# PIC32MZ.net
KiCad netlist of a schematic drawn in Altium Designer
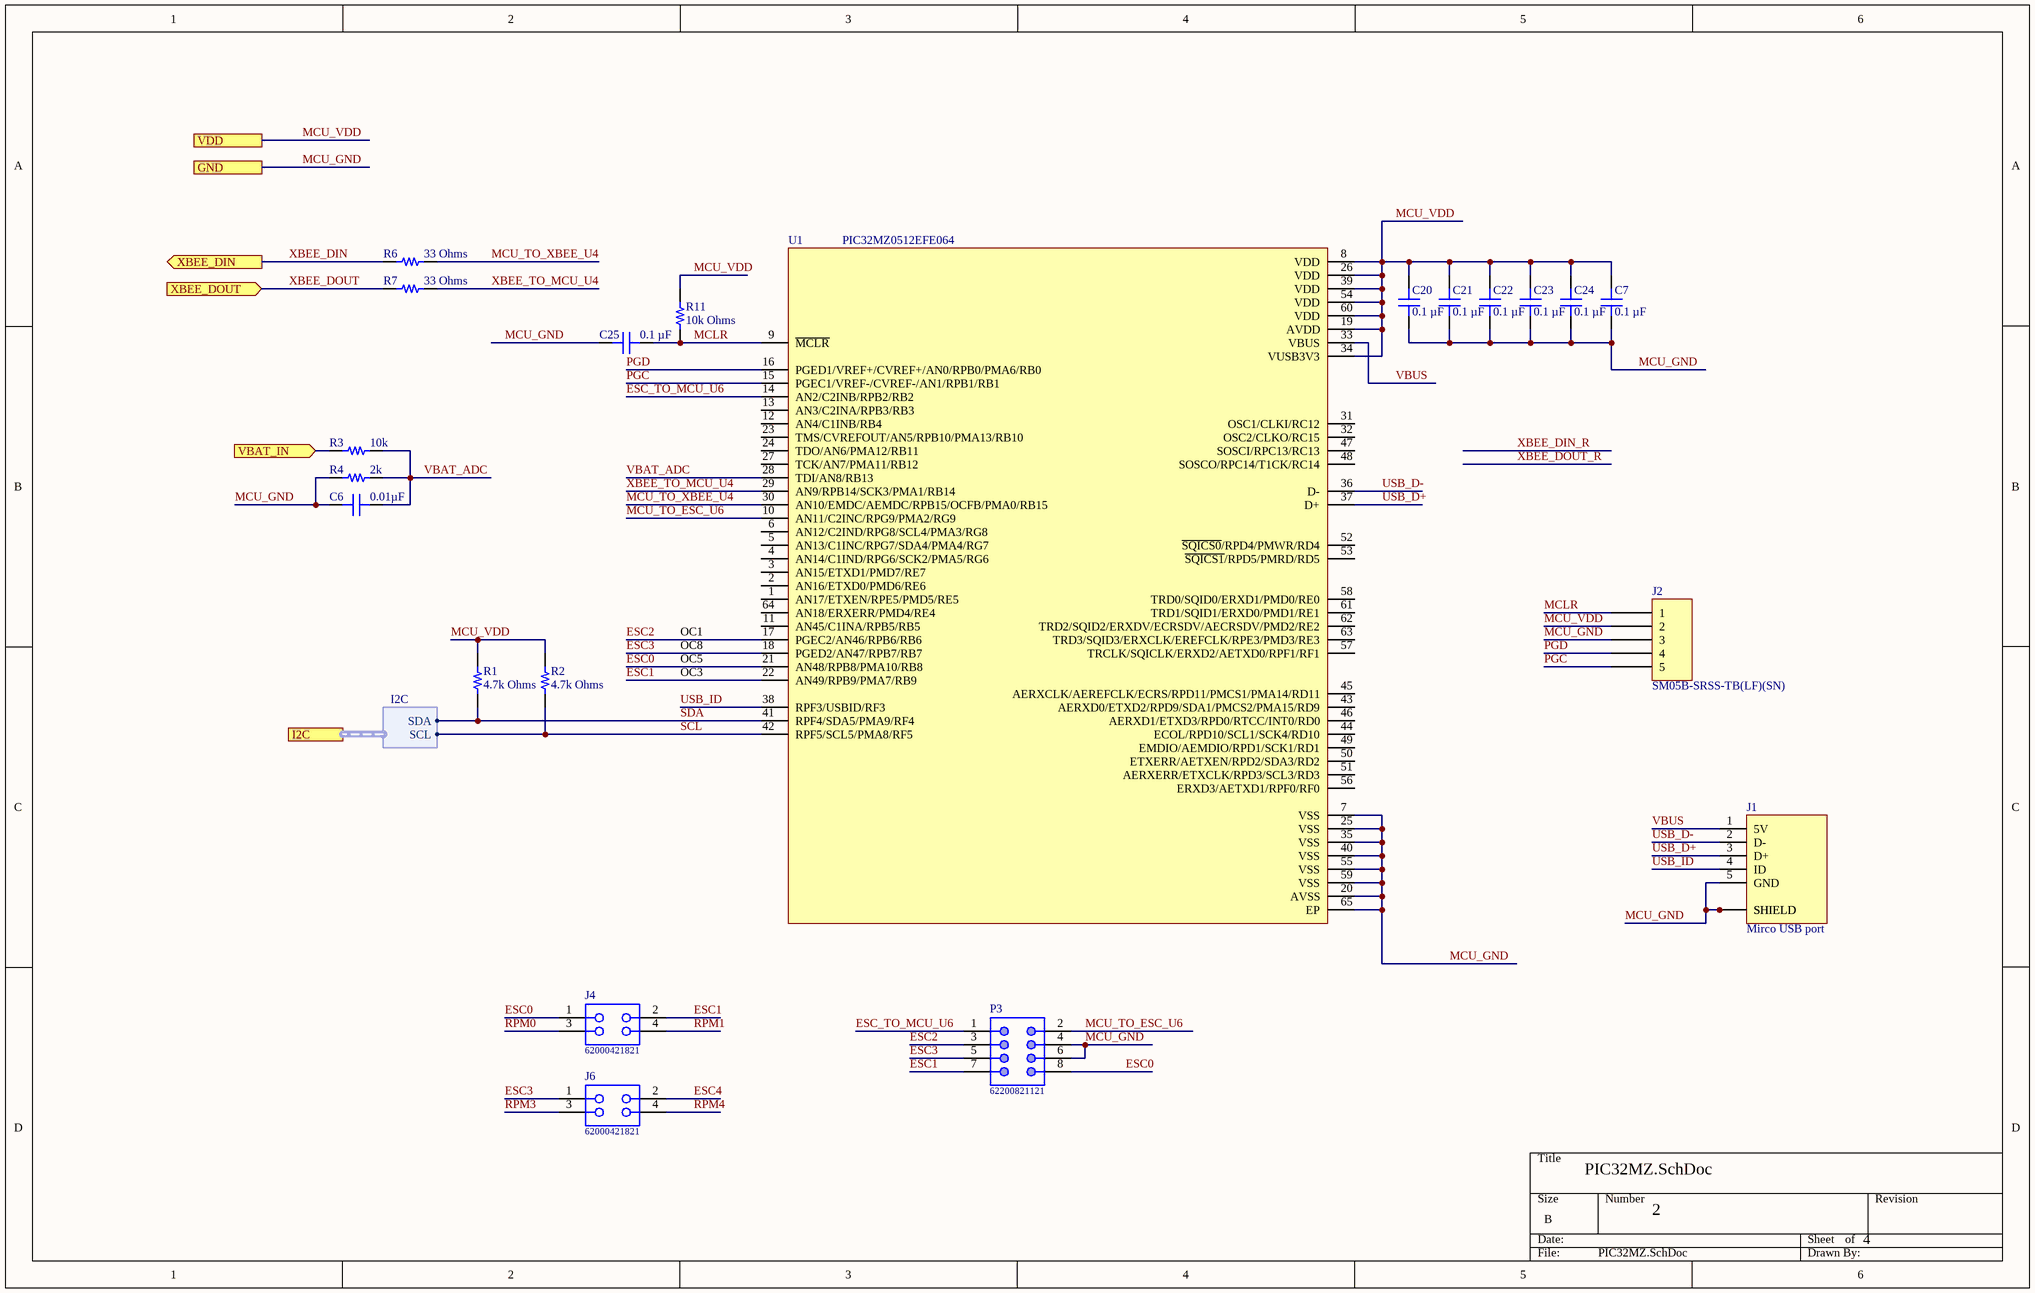
[diagram p0: PIC32MZ.SchDoc]

(export (version "E")
  (design (tool "Eeschema 10.0.6"))
  (components
    (comp (ref "C6")
      (value "0.01µF")
      (footprint "CAP 0603_1608")
      (description "CAP CER 0.1UF 100V 0603 EPOXY")
      (fields
        (field (name "PART NUMBER") "GCG188R92A104KA03D")
        (field (name "MANUFACTURER") "Murata Electronics")
      )
      (libsource (lib "Celestial Altium Library - altium_library") (part "Capacitor"))
    )
    (comp (ref "C7")
      (value "0.1 µF")
      (footprint "CAP 0402_1005")
      (description "CAP CER 0.1UF 16V X7R 0402")
      (fields (field (name "PART NUMBER") "C0402C104K4RACAUTO") (field (name "MANUFACTURER") "KEMET"))
      (libsource (lib "Celestial Altium Library - altium_library") (part "Capacitor"))
    )
    (comp (ref "C20")
      (value "0.1 µF")
      (footprint "CAP 0402_1005")
      (description "CAP CER 0.1UF 16V X7R 0402")
      (fields (field (name "PART NUMBER") "C0402C104K4RACAUTO") (field (name "MANUFACTURER") "KEMET"))
      (libsource (lib "Celestial Altium Library - altium_library") (part "Capacitor"))
    )
    (comp (ref "C21")
      (value "0.1 µF")
      (footprint "CAP 0402_1005")
      (description "CAP CER 0.1UF 16V X7R 0402")
      (fields (field (name "PART NUMBER") "C0402C104K4RACAUTO") (field (name "MANUFACTURER") "KEMET"))
      (libsource (lib "Celestial Altium Library - altium_library") (part "Capacitor"))
    )
    (comp (ref "C22")
      (value "0.1 µF")
      (footprint "CAP 0402_1005")
      (description "CAP CER 0.1UF 16V X7R 0402")
      (fields (field (name "PART NUMBER") "C0402C104K4RACAUTO") (field (name "MANUFACTURER") "KEMET"))
      (libsource (lib "Celestial Altium Library - altium_library") (part "Capacitor"))
    )
    (comp (ref "C23")
      (value "0.1 µF")
      (footprint "CAP 0402_1005")
      (description "CAP CER 0.1UF 16V X7R 0402")
      (fields (field (name "PART NUMBER") "C0402C104K4RACAUTO") (field (name "MANUFACTURER") "KEMET"))
      (libsource (lib "Celestial Altium Library - altium_library") (part "Capacitor"))
    )
    (comp (ref "C24")
      (value "0.1 µF")
      (footprint "CAP 0402_1005")
      (description "CAP CER 0.1UF 16V X7R 0402")
      (fields (field (name "PART NUMBER") "C0402C104K4RACAUTO") (field (name "MANUFACTURER") "KEMET"))
      (libsource (lib "Celestial Altium Library - altium_library") (part "Capacitor"))
    )
    (comp (ref "C25")
      (value "0.1 µF")
      (footprint "CAP 0402_1005")
      (description "CAP CER 0.1UF 16V X7R 0402")
      (fields (field (name "PART NUMBER") "C0402C104K4RACAUTO") (field (name "MANUFACTURER") "KEMET"))
      (libsource (lib "Celestial Altium Library - altium_library") (part "Capacitor"))
    )
    (comp (ref "J1")
      (value "Mirco USB port")
      (footprint "AMPHENOL_10118194-0001LF")
      (description "USB - micro B USB 2.0 Receptacle Connector 5 Position Surface Mount, Right Angle; Through Hole")
      (fields (field (name "MF") "Amphenol ICC") (field (name "MP") "10118194-0001LF"))
      (libsource (lib "IC") (part "10118194-0001LF"))
    )
    (comp (ref "J2")
      (value "SM05B-SRSS-TB(LF)(SN)")
      (footprint "JST SM05B-SRSS-TB")
      (description "CONN HEADER SMD R/A 5POS 1MM")
      (fields (field (name "MANUFACTURER") "JST Sales America Inc."))
      (libsource (lib "Celestial Altium Library - altium_library") (part "5 Pin"))
    )
    (comp (ref "J4")
      (value "62000421821")
      (footprint "62000421821")
      (description "WR-PHD Socket Header, THT, pitch 2mm, Dual Row, Vertical, 4p")
      (fields (field (name "MANUFACTURER") "Wurth Elektronik"))
      (libsource (lib "Altium_WR-PHD") (part "62000421821"))
    )
    (comp (ref "J6")
      (value "62000421821")
      (footprint "62000421821")
      (description "WR-PHD Socket Header, THT, pitch 2mm, Dual Row, Vertical, 4p")
      (fields (field (name "MANUFACTURER") "Wurth Elektronik"))
      (libsource (lib "Altium_WR-PHD") (part "62000421821"))
    )
    (comp (ref "P3")
      (value "62200821121")
      (footprint "62200821121")
      (description "WR-PHD Pin Header, THT, pitch 1.27mm, Dual Row, Vertical, 8p")
      (fields (field (name "MANUFACTURER") "Wurth Elektronik"))
      (libsource (lib "Altium_WR-PHD") (part "62200821121"))
    )
    (comp (ref "R1")
      (value "4.7k Ohms")
      (footprint "RES 0402_1005")
      (description "RES 330 OHM 5% 1/16W 0402")
      (fields (field (name "PART NUMBER") "CRCW0402330RJNEDC") (field (name "MANUFACTURER") "Vishay Dale"))
      (libsource (lib "Celestial Altium Library - altium_library") (part "Resistor"))
    )
    (comp (ref "R2")
      (value "4.7k Ohms")
      (footprint "RES 0402_1005")
      (description "RES 330 OHM 5% 1/16W 0402")
      (fields (field (name "PART NUMBER") "CRCW0402330RJNEDC") (field (name "MANUFACTURER") "Vishay Dale"))
      (libsource (lib "Celestial Altium Library - altium_library") (part "Resistor"))
    )
    (comp (ref "R3")
      (value "10k")
      (footprint "RES 0603_1608")
      (description "RES SMD 21.5 OHM 1% 1/10W 0603")
      (fields
        (field (name "PART NUMBER") "ERJ-3EKF21R5V")
        (field (name "MANUFACTURER") "Panasonic Electronic Components")
      )
      (libsource (lib "Celestial Altium Library - altium_library") (part "Resistor"))
    )
    (comp (ref "R4")
      (value "2k")
      (footprint "RES 0603_1608")
      (description "RES SMD 21.5 OHM 1% 1/10W 0603")
      (fields
        (field (name "PART NUMBER") "ERJ-3EKF21R5V")
        (field (name "MANUFACTURER") "Panasonic Electronic Components")
      )
      (libsource (lib "Celestial Altium Library - altium_library") (part "Resistor"))
    )
    (comp (ref "R6")
      (value "33 Ohms")
      (footprint "RES 0402_1005")
      (description "RES 330 OHM 5% 1/16W 0402")
      (fields (field (name "PART NUMBER") "CRCW0402330RJNEDC") (field (name "MANUFACTURER") "Vishay Dale"))
      (libsource (lib "Celestial Altium Library - altium_library") (part "Resistor"))
    )
    (comp (ref "R7")
      (value "33 Ohms")
      (footprint "RES 0402_1005")
      (description "RES 330 OHM 5% 1/16W 0402")
      (fields (field (name "PART NUMBER") "CRCW0402330RJNEDC") (field (name "MANUFACTURER") "Vishay Dale"))
      (libsource (lib "Celestial Altium Library - altium_library") (part "Resistor"))
    )
    (comp (ref "R11")
      (value "10k Ohms")
      (footprint "RES 0402_1005")
      (description "RES 330 OHM 5% 1/16W 0402")
      (fields (field (name "PART NUMBER") "CRCW0402330RJNEDC") (field (name "MANUFACTURER") "Vishay Dale"))
      (libsource (lib "Celestial Altium Library - altium_library") (part "Resistor"))
    )
    (comp (ref "U1")
      (value "PIC32MZ0512EFE064")
      (footprint "QFN50P900X900X100-65N")
      (description "32-bit Microcontrollers - MCU 32-BIT MCU 512KB FL 128KB RAM, No Crypto")
      (fields (field (name "MF") "Microchip") (field (name "MP") "PIC32MZ2048EFG064T-I/PT"))
      (libsource (lib "IC") (part "PIC32MZ0512EFE064-I/PT"))
    )
  )
  (nets
    (net (code "2") (name "/ESC0") (class "Default")
      (node (ref "J4") (pin "1") (pinfunction "1_1") (pintype "passive"))
      (node (ref "P3") (pin "8") (pinfunction "8_8") (pintype "passive"))
      (node (ref "U1") (pin "21") (pinfunction "AN48/RPB8/PMA10/RB8_21") (pintype "passive"))
    )
    (net (code "3") (name "/ESC1") (class "Default")
      (node (ref "J4") (pin "2") (pinfunction "2_2") (pintype "passive"))
      (node (ref "P3") (pin "7") (pinfunction "7_7") (pintype "passive"))
      (node (ref "U1") (pin "22") (pinfunction "AN49/RPB9/PMA7/RB9_22") (pintype "passive"))
    )
    (net (code "4") (name "/ESC2") (class "Default")
      (node (ref "P3") (pin "3") (pinfunction "3_3") (pintype "passive"))
      (node (ref "U1") (pin "17") (pinfunction "PGEC2/AN46/RPB6/RB6_17") (pintype "passive"))
    )
    (net (code "5") (name "/ESC3") (class "Default")
      (node (ref "J6") (pin "1") (pinfunction "1_1") (pintype "passive"))
      (node (ref "P3") (pin "5") (pinfunction "5_5") (pintype "passive"))
      (node (ref "U1") (pin "18") (pinfunction "PGED2/AN47/RPB7/RB7_18") (pintype "passive"))
    )
    (net (code "6") (name "/ESC4") (class "Default")
      (node (ref "J6") (pin "2") (pinfunction "2_2") (pintype "passive"))
    )
    (net (code "7") (name "/ESC_TO_MCU_U6") (class "Default")
      (node (ref "P3") (pin "1") (pinfunction "1_1") (pintype "passive"))
      (node (ref "U1") (pin "14") (pinfunction "AN2/C2INB/RPB2/RB2_14") (pintype "passive"))
    )
    (net (code "8") (name "/MCLR") (class "Default")
      (node (ref "C25") (pin "1") (pinfunction "1_1") (pintype "passive"))
      (node (ref "J2") (pin "1") (pinfunction "1_1") (pintype "passive"))
      (node (ref "R11") (pin "1") (pinfunction "1_1") (pintype "passive"))
      (node (ref "U1") (pin "9") (pinfunction "~{MCLR}_9") (pintype "passive"))
    )
    (net (code "9") (name "/MCU_GND") (class "Default")
      (node (ref "C20") (pin "1") (pinfunction "1_1") (pintype "passive"))
      (node (ref "C21") (pin "1") (pinfunction "1_1") (pintype "passive"))
      (node (ref "C22") (pin "1") (pinfunction "1_1") (pintype "passive"))
      (node (ref "C23") (pin "1") (pinfunction "1_1") (pintype "passive"))
      (node (ref "C24") (pin "1") (pinfunction "1_1") (pintype "passive"))
      (node (ref "C25") (pin "2") (pinfunction "2_2") (pintype "passive"))
      (node (ref "C6") (pin "2") (pinfunction "2_2") (pintype "passive"))
      (node (ref "C7") (pin "1") (pinfunction "1_1") (pintype "passive"))
      (node (ref "J1") (pin "5") (pinfunction "GND_5") (pintype "passive"))
      (node (ref "J1") (pin "S1") (pinfunction "SHIELD_S1") (pintype "passive"))
      (node (ref "J1") (pin "S2") (pinfunction "SHIELD_S2") (pintype "passive"))
      (node (ref "J1") (pin "S3") (pinfunction "SHIELD_S3") (pintype "passive"))
      (node (ref "J1") (pin "S4") (pinfunction "SHIELD_S4") (pintype "passive"))
      (node (ref "J1") (pin "S5") (pinfunction "SHIELD_S5") (pintype "passive"))
      (node (ref "J1") (pin "S6") (pinfunction "SHIELD_S6") (pintype "passive"))
      (node (ref "J2") (pin "3") (pinfunction "3_3") (pintype "passive"))
      (node (ref "P3") (pin "4") (pinfunction "4_4") (pintype "passive"))
      (node (ref "P3") (pin "6") (pinfunction "6_6") (pintype "passive"))
      (node (ref "R4") (pin "1") (pinfunction "1_1") (pintype "passive"))
      (node (ref "U1") (pin "20") (pinfunction "AVSS_20") (pintype "power_in"))
      (node (ref "U1") (pin "25") (pinfunction "VSS_25") (pintype "power_in"))
      (node (ref "U1") (pin "35") (pinfunction "VSS_35") (pintype "power_in"))
      (node (ref "U1") (pin "40") (pinfunction "VSS_40") (pintype "power_in"))
      (node (ref "U1") (pin "55") (pinfunction "VSS_55") (pintype "power_in"))
      (node (ref "U1") (pin "59") (pinfunction "VSS_59") (pintype "power_in"))
      (node (ref "U1") (pin "65") (pinfunction "EP_65") (pintype "power_in"))
      (node (ref "U1") (pin "7") (pinfunction "VSS_7") (pintype "power_in"))
    )
    (net (code "10") (name "/MCU_TO_ESC_U6") (class "Default")
      (node (ref "P3") (pin "2") (pinfunction "2_2") (pintype "passive"))
      (node (ref "U1") (pin "10") (pinfunction "AN11/C2INC/RPG9/PMA2/RG9_10") (pintype "passive"))
    )
    (net (code "11") (name "/MCU_TO_XBEE_U4") (class "Default")
      (node (ref "R6") (pin "2") (pinfunction "2_2") (pintype "passive"))
      (node (ref "U1") (pin "30") (pinfunction "AN10/EMDC/AEMDC/RPB15/OCFB/PMA0/RB15_30") (pintype "passive"))
    )
    (net (code "12") (name "/MCU_VDD") (class "Default")
      (node (ref "C20") (pin "2") (pinfunction "2_2") (pintype "passive"))
      (node (ref "C21") (pin "2") (pinfunction "2_2") (pintype "passive"))
      (node (ref "C22") (pin "2") (pinfunction "2_2") (pintype "passive"))
      (node (ref "C23") (pin "2") (pinfunction "2_2") (pintype "passive"))
      (node (ref "C24") (pin "2") (pinfunction "2_2") (pintype "passive"))
      (node (ref "C7") (pin "2") (pinfunction "2_2") (pintype "passive"))
      (node (ref "J2") (pin "2") (pinfunction "2_2") (pintype "passive"))
      (node (ref "R1") (pin "2") (pinfunction "2_2") (pintype "passive"))
      (node (ref "R11") (pin "2") (pinfunction "2_2") (pintype "passive"))
      (node (ref "R2") (pin "2") (pinfunction "2_2") (pintype "passive"))
      (node (ref "U1") (pin "19") (pinfunction "AVDD_19") (pintype "power_in"))
      (node (ref "U1") (pin "26") (pinfunction "VDD_26") (pintype "power_in"))
      (node (ref "U1") (pin "34") (pinfunction "VUSB3V3_34") (pintype "power_in"))
      (node (ref "U1") (pin "39") (pinfunction "VDD_39") (pintype "power_in"))
      (node (ref "U1") (pin "54") (pinfunction "VDD_54") (pintype "power_in"))
      (node (ref "U1") (pin "60") (pinfunction "VDD_60") (pintype "power_in"))
      (node (ref "U1") (pin "8") (pinfunction "VDD_8") (pintype "power_in"))
    )
    (net (code "13") (name "/PGC") (class "Default")
      (node (ref "J2") (pin "5") (pinfunction "5_5") (pintype "passive"))
      (node (ref "U1") (pin "15") (pinfunction "PGEC1/VREF-/CVREF-/AN1/RPB1/RB1_15") (pintype "passive"))
    )
    (net (code "14") (name "/PGD") (class "Default")
      (node (ref "J2") (pin "4") (pinfunction "4_4") (pintype "passive"))
      (node (ref "U1") (pin "16") (pinfunction "PGED1/VREF+/CVREF+/AN0/RPB0/PMA6/RB0_16") (pintype "passive"))
    )
    (net (code "15") (name "/RPM0") (class "Default")
      (node (ref "J4") (pin "3") (pinfunction "3_3") (pintype "passive"))
    )
    (net (code "16") (name "/RPM1") (class "Default")
      (node (ref "J4") (pin "4") (pinfunction "4_4") (pintype "passive"))
    )
    (net (code "17") (name "/RPM3") (class "Default")
      (node (ref "J6") (pin "3") (pinfunction "3_3") (pintype "passive"))
    )
    (net (code "18") (name "/RPM4") (class "Default")
      (node (ref "J6") (pin "4") (pinfunction "4_4") (pintype "passive"))
    )
    (net (code "19") (name "/SCL") (class "Default")
      (node (ref "R2") (pin "1") (pinfunction "1_1") (pintype "passive"))
      (node (ref "U1") (pin "42") (pinfunction "RPF5/SCL5/PMA8/RF5_42") (pintype "passive"))
    )
    (net (code "20") (name "/SDA") (class "Default")
      (node (ref "R1") (pin "1") (pinfunction "1_1") (pintype "passive"))
      (node (ref "U1") (pin "41") (pinfunction "RPF4/SDA5/PMA9/RF4_41") (pintype "passive"))
    )
    (net (code "21") (name "/USB_D+") (class "Default")
      (node (ref "J1") (pin "3") (pinfunction "D+_3") (pintype "passive"))
      (node (ref "U1") (pin "37") (pinfunction "D+_37") (pintype "passive"))
    )
    (net (code "22") (name "/USB_D-") (class "Default")
      (node (ref "J1") (pin "2") (pinfunction "D-_2") (pintype "passive"))
      (node (ref "U1") (pin "36") (pinfunction "D-_36") (pintype "passive"))
    )
    (net (code "23") (name "/USB_ID") (class "Default")
      (node (ref "J1") (pin "4") (pinfunction "ID_4") (pintype "passive"))
      (node (ref "U1") (pin "38") (pinfunction "RPF3/USBID/RF3_38") (pintype "passive"))
    )
    (net (code "24") (name "/VBAT_ADC") (class "Default")
      (node (ref "C6") (pin "1") (pinfunction "1_1") (pintype "passive"))
      (node (ref "R3") (pin "1") (pinfunction "1_1") (pintype "passive"))
      (node (ref "R4") (pin "2") (pinfunction "2_2") (pintype "passive"))
      (node (ref "U1") (pin "28") (pinfunction "TDI/AN8/RB13_28") (pintype "passive"))
    )
    (net (code "25") (name "/VBAT_IN") (class "Default")
      (node (ref "R3") (pin "2") (pinfunction "2_2") (pintype "passive"))
    )
    (net (code "26") (name "/VBUS") (class "Default")
      (node (ref "J1") (pin "1") (pinfunction "5V_1") (pintype "passive"))
      (node (ref "U1") (pin "33") (pinfunction "VBUS_33") (pintype "power_in"))
    )
    (net (code "27") (name "/XBEE_DIN") (class "Default")
      (node (ref "R6") (pin "1") (pinfunction "1_1") (pintype "passive"))
    )
    (net (code "29") (name "/XBEE_DOUT") (class "Default")
      (node (ref "R7") (pin "1") (pinfunction "1_1") (pintype "passive"))
    )
    (net (code "31") (name "/XBEE_TO_MCU_U4") (class "Default")
      (node (ref "R7") (pin "2") (pinfunction "2_2") (pintype "passive"))
      (node (ref "U1") (pin "29") (pinfunction "AN9/RPB14/SCK3/PMA1/RB14_29") (pintype "passive"))
    )
    (net (code "33") (name "unconnected-(U1-AERXCLK{slash}AEREFCLK{slash}ECRS{slash}RPD11{slash}PMCS1{slash}PMA14{slash}RD11-Pad45)") (class "Default")
      (node (ref "U1") (pin "45") (pinfunction "AERXCLK/AEREFCLK/ECRS/RPD11/PMCS1/PMA14/RD11_45") (pintype "passive"))
    )
    (net (code "34") (name "unconnected-(U1-AERXD0{slash}ETXD2{slash}RPD9{slash}SDA1{slash}PMCS2{slash}PMA15{slash}RD9-Pad43)") (class "Default")
      (node (ref "U1") (pin "43") (pinfunction "AERXD0/ETXD2/RPD9/SDA1/PMCS2/PMA15/RD9_43") (pintype "passive"))
    )
    (net (code "35") (name "unconnected-(U1-AERXD1{slash}ETXD3{slash}RPD0{slash}RTCC{slash}INT0{slash}RD0-Pad46)") (class "Default")
      (node (ref "U1") (pin "46") (pinfunction "AERXD1/ETXD3/RPD0/RTCC/INT0/RD0_46") (pintype "passive"))
    )
    (net (code "36") (name "unconnected-(U1-AERXERR{slash}ETXCLK{slash}RPD3{slash}SCL3{slash}RD3-Pad51)") (class "Default")
      (node (ref "U1") (pin "51") (pinfunction "AERXERR/ETXCLK/RPD3/SCL3/RD3_51") (pintype "passive"))
    )
    (net (code "37") (name "unconnected-(U1-AN3{slash}C2INA{slash}RPB3{slash}RB3-Pad13)") (class "Default")
      (node (ref "U1") (pin "13") (pinfunction "AN3/C2INA/RPB3/RB3_13") (pintype "passive"))
    )
    (net (code "38") (name "unconnected-(U1-AN4{slash}C1INB{slash}RB4-Pad12)") (class "Default")
      (node (ref "U1") (pin "12") (pinfunction "AN4/C1INB/RB4_12") (pintype "passive"))
    )
    (net (code "39") (name "unconnected-(U1-AN12{slash}C2IND{slash}RPG8{slash}SCL4{slash}PMA3{slash}RG8-Pad6)") (class "Default")
      (node (ref "U1") (pin "6") (pinfunction "AN12/C2IND/RPG8/SCL4/PMA3/RG8_6") (pintype "passive"))
    )
    (net (code "40") (name "unconnected-(U1-AN13{slash}C1INC{slash}RPG7{slash}SDA4{slash}PMA4{slash}RG7-Pad5)") (class "Default")
      (node (ref "U1") (pin "5") (pinfunction "AN13/C1INC/RPG7/SDA4/PMA4/RG7_5") (pintype "passive"))
    )
    (net (code "41") (name "unconnected-(U1-AN14{slash}C1IND{slash}RPG6{slash}SCK2{slash}PMA5{slash}RG6-Pad4)") (class "Default")
      (node (ref "U1") (pin "4") (pinfunction "AN14/C1IND/RPG6/SCK2/PMA5/RG6_4") (pintype "passive"))
    )
    (net (code "42") (name "unconnected-(U1-AN15{slash}ETXD1{slash}PMD7{slash}RE7-Pad3)") (class "Default")
      (node (ref "U1") (pin "3") (pinfunction "AN15/ETXD1/PMD7/RE7_3") (pintype "passive"))
    )
    (net (code "43") (name "unconnected-(U1-AN16{slash}ETXD0{slash}PMD6{slash}RE6-Pad2)") (class "Default")
      (node (ref "U1") (pin "2") (pinfunction "AN16/ETXD0/PMD6/RE6_2") (pintype "passive"))
    )
    (net (code "44") (name "unconnected-(U1-AN17{slash}ETXEN{slash}RPE5{slash}PMD5{slash}RE5-Pad1)") (class "Default")
      (node (ref "U1") (pin "1") (pinfunction "AN17/ETXEN/RPE5/PMD5/RE5_1") (pintype "passive"))
    )
    (net (code "45") (name "unconnected-(U1-AN18{slash}ERXERR{slash}PMD4{slash}RE4-Pad64)") (class "Default")
      (node (ref "U1") (pin "64") (pinfunction "AN18/ERXERR/PMD4/RE4_64") (pintype "passive"))
    )
    (net (code "46") (name "unconnected-(U1-AN45{slash}C1INA{slash}RPB5{slash}RB5-Pad11)") (class "Default")
      (node (ref "U1") (pin "11") (pinfunction "AN45/C1INA/RPB5/RB5_11") (pintype "passive"))
    )
    (net (code "47") (name "unconnected-(U1-ECOL{slash}RPD10{slash}SCL1{slash}SCK4{slash}RD10-Pad44)") (class "Default")
      (node (ref "U1") (pin "44") (pinfunction "ECOL/RPD10/SCL1/SCK4/RD10_44") (pintype "passive"))
    )
    (net (code "48") (name "unconnected-(U1-EMDIO{slash}AEMDIO{slash}RPD1{slash}SCK1{slash}RD1-Pad49)") (class "Default")
      (node (ref "U1") (pin "49") (pinfunction "EMDIO/AEMDIO/RPD1/SCK1/RD1_49") (pintype "passive"))
    )
    (net (code "49") (name "unconnected-(U1-ERXD3{slash}AETXD1{slash}RPF0{slash}RF0-Pad56)") (class "Default")
      (node (ref "U1") (pin "56") (pinfunction "ERXD3/AETXD1/RPF0/RF0_56") (pintype "passive"))
    )
    (net (code "50") (name "unconnected-(U1-ETXERR{slash}AETXEN{slash}RPD2{slash}SDA3{slash}RD2-Pad50)") (class "Default")
      (node (ref "U1") (pin "50") (pinfunction "ETXERR/AETXEN/RPD2/SDA3/RD2_50") (pintype "passive"))
    )
    (net (code "51") (name "unconnected-(U1-OSC1{slash}CLKI{slash}RC12-Pad31)") (class "Default")
      (node (ref "U1") (pin "31") (pinfunction "OSC1/CLKI/RC12_31") (pintype "passive"))
    )
    (net (code "52") (name "unconnected-(U1-OSC2{slash}CLKO{slash}RC15-Pad32)") (class "Default")
      (node (ref "U1") (pin "32") (pinfunction "OSC2/CLKO/RC15_32") (pintype "passive"))
    )
    (net (code "53") (name "unconnected-(U1-SOSCI{slash}RPC13{slash}RC13-Pad47)") (class "Default")
      (node (ref "U1") (pin "47") (pinfunction "SOSCI/RPC13/RC13_47") (pintype "passive"))
    )
    (net (code "54") (name "unconnected-(U1-SOSCO{slash}RPC14{slash}T1CK{slash}RC14-Pad48)") (class "Default")
      (node (ref "U1") (pin "48") (pinfunction "SOSCO/RPC14/T1CK/RC14_48") (pintype "passive"))
    )
    (net (code "55") (name "unconnected-(U1-TCK{slash}AN7{slash}PMA11{slash}RB12-Pad27)") (class "Default")
      (node (ref "U1") (pin "27") (pinfunction "TCK/AN7/PMA11/RB12_27") (pintype "passive"))
    )
    (net (code "56") (name "unconnected-(U1-TDO{slash}AN6{slash}PMA12{slash}RB11-Pad24)") (class "Default")
      (node (ref "U1") (pin "24") (pinfunction "TDO/AN6/PMA12/RB11_24") (pintype "passive"))
    )
    (net (code "57") (name "unconnected-(U1-TMS{slash}CVREFOUT{slash}AN5{slash}RPB10{slash}PMA13{slash}RB10-Pad23)") (class "Default")
      (node (ref "U1") (pin "23") (pinfunction "TMS/CVREFOUT/AN5/RPB10/PMA13/RB10_23") (pintype "passive"))
    )
    (net (code "58") (name "unconnected-(U1-TRCLK{slash}SQICLK{slash}ERXD2{slash}AETXD0{slash}RPF1{slash}RF1-Pad57)") (class "Default")
      (node (ref "U1") (pin "57") (pinfunction "TRCLK/SQICLK/ERXD2/AETXD0/RPF1/RF1_57") (pintype "passive"))
    )
    (net (code "59") (name "unconnected-(U1-TRD0{slash}SQID0{slash}ERXD1{slash}PMD0{slash}RE0-Pad58)") (class "Default")
      (node (ref "U1") (pin "58") (pinfunction "TRD0/SQID0/ERXD1/PMD0/RE0_58") (pintype "passive"))
    )
    (net (code "60") (name "unconnected-(U1-TRD1{slash}SQID1{slash}ERXD0{slash}PMD1{slash}RE1-Pad61)") (class "Default")
      (node (ref "U1") (pin "61") (pinfunction "TRD1/SQID1/ERXD0/PMD1/RE1_61") (pintype "passive"))
    )
    (net (code "61") (name "unconnected-(U1-TRD2{slash}SQID2{slash}ERXDV{slash}ECRSDV{slash}AECRSDV{slash}PMD2{slash}RE2-Pad62)") (class "Default")
      (node (ref "U1") (pin "62") (pinfunction "TRD2/SQID2/ERXDV/ECRSDV/AECRSDV/PMD2/RE2_62") (pintype "passive"))
    )
    (net (code "62") (name "unconnected-(U1-TRD3{slash}SQID3{slash}ERXCLK{slash}EREFCLK{slash}RPE3{slash}PMD3{slash}RE3-Pad63)") (class "Default")
      (node (ref "U1") (pin "63") (pinfunction "TRD3/SQID3/ERXCLK/EREFCLK/RPE3/PMD3/RE3_63") (pintype "passive"))
    )
    (net (code "63") (name "unconnected-(U1-~{SQICS0}{slash}RPD4{slash}PMWR{slash}RD4-Pad52)") (class "Default")
      (node (ref "U1") (pin "52") (pinfunction "~{SQICS0}/RPD4/PMWR/RD4_52") (pintype "passive"))
    )
    (net (code "64") (name "unconnected-(U1-~{SQICS1}{slash}RPD5{slash}PMRD{slash}RD5-Pad53)") (class "Default")
      (node (ref "U1") (pin "53") (pinfunction "~{SQICS1}/RPD5/PMRD/RD5_53") (pintype "passive"))
    )
  )
)
